# Power.net
KiCad netlist of a schematic drawn in Altium Designer
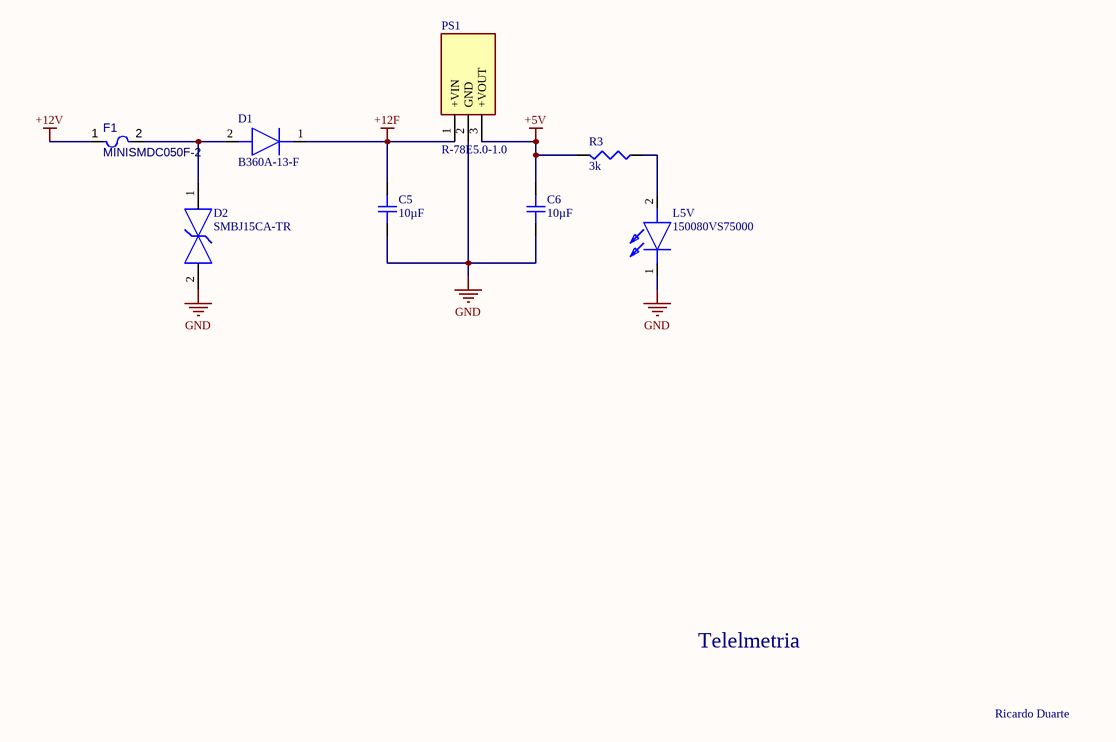
[diagram p0: Power.SchDoc]

(export (version "E")
  (design (tool "Eeschema 10.0.6"))
  (components
    (comp (ref "C5")
      (value "10µF")
      (footprint "CAP_0805")
      (fields (field (name "Comment") "10uF") (field (name "SOURCE") "Schematic-Lib-PhilsLab.SchLib"))
      (libsource (lib "EMEA- ISEL Formula Student-Instituto Superior Tecnico - Universidade de Lisboa") (part "10uF"))
    )
    (comp (ref "C6")
      (value "10µF")
      (footprint "CAP_0805")
      (fields (field (name "Comment") "10uF") (field (name "SOURCE") "Schematic-Lib-PhilsLab.SchLib"))
      (libsource (lib "EMEA- ISEL Formula Student-Instituto Superior Tecnico - Universidade de Lisboa") (part "10uF"))
    )
    (comp (ref "D1")
      (value "B360A-13-F")
      (footprint "DIOM5226X240N")
      (description "Diode")
      (fields (field (name "MOUSER PART NUMBER") "621-B360A-F"))
      (libsource (lib "EMEA- ISEL Formula Student-Instituto Superior Tecnico - Universidade de Lisboa") (part "B360A-13-F"))
    )
    (comp (ref "D2")
      (value "SMBJ15CA-TR")
      (footprint "FP-SMB-CA-MFG")
      (description "Trans Voltage Suppressor Diode, 4000W, 15V V(RWM), Bidirectional, 1 Element, Silicon, DO-214AA")
      (libsource (lib "EMEA- ISEL Formula Student-Instituto Superior Tecnico - Universidade de Lisboa") (part "89c663e49c8877d2c9d183c2997548d"))
    )
    (comp (ref "F1")
      (value "MINISMDC050F-2")
      (footprint "MINISMDC050F-2-Footprint-1")
      (description "PTC Resettable Fuse, 24V, Surface Mount")
      (libsource (lib "EMEA- ISEL Formula Student-Instituto Superior Tecnico - Universidade de Lisboa") (part "FUSE-2"))
    )
    (comp (ref "L5V")
      (value "150080VS75000")
      (footprint "LEDC2012X80N")
      (description "Single Color LED, Bright Green, Water Clear, 1.4mm")
      (fields (field (name "MOUSER PART NUMBER") "710-150080VS75000"))
      (libsource (lib "EMEA- ISEL Formula Student-Instituto Superior Tecnico - Universidade de Lisboa") (part "150080VS75000"))
    )
    (comp (ref "PS1")
      (value "R-78E5.0-1.0")
      (footprint "SamacSys:R78E5010")
      (description "Power Supply")
      (fields (field (name "MOUSER PART NUMBER") "919-R-78E5.0-1.0"))
      (libsource (lib "*") (part "R-78E5.0-1.0"))
    )
    (comp (ref "R3")
      (value "3k")
      (footprint "RES_0805")
      (description "Resistor SMD 0805 4,7K")
      (fields (field (name "Comment") "4K7") (field (name "SOURCE") "Schematic-Lib-PhilsLab.SchLib"))
      (libsource (lib "EMEA- ISEL Formula Student-Instituto Superior Tecnico - Universidade de Lisboa") (part "RES_5931"))
    )
  )
  (nets
    (net (code "1") (name "+5V") (class "Default")
      (node (ref "C6") (pin "2") (pinfunction "2_2") (pintype "passive"))
      (node (ref "PS1") (pin "3") (pinfunction "+VOUT_3") (pintype "passive"))
      (node (ref "R3") (pin "2") (pinfunction "2_2") (pintype "passive"))
    )
    (net (code "2") (name "+12F") (class "Default")
      (node (ref "C5") (pin "2") (pinfunction "2_2") (pintype "passive"))
      (node (ref "D1") (pin "1") (pinfunction "K_1") (pintype "passive"))
      (node (ref "PS1") (pin "1") (pinfunction "+VIN_1") (pintype "passive"))
    )
    (net (code "3") (name "+12V") (class "Default")
      (node (ref "F1") (pin "1") (pinfunction "1_1") (pintype "passive"))
    )
    (net (code "4") (name "GND") (class "Default")
      (node (ref "C5") (pin "1") (pinfunction "1_1") (pintype "passive"))
      (node (ref "C6") (pin "1") (pinfunction "1_1") (pintype "passive"))
      (node (ref "D2") (pin "2") (pinfunction "2_2") (pintype "passive"))
      (node (ref "L5V") (pin "1") (pinfunction "K_1") (pintype "passive"))
      (node (ref "PS1") (pin "2") (pinfunction "GND_2") (pintype "passive"))
    )
    (net (code "5") (name "Net-(D1-A)") (class "Default")
      (node (ref "D1") (pin "2") (pinfunction "A_2") (pintype "passive"))
      (node (ref "D2") (pin "1") (pinfunction "1_1") (pintype "passive"))
      (node (ref "F1") (pin "2") (pinfunction "2_2") (pintype "passive"))
    )
    (net (code "6") (name "Net-(L5V-A)") (class "Default")
      (node (ref "L5V") (pin "2") (pinfunction "A_2") (pintype "passive"))
      (node (ref "R3") (pin "1") (pinfunction "1_1") (pintype "passive"))
    )
  )
)
